# Bus_Definition_V1_2.net
KiCad netlist of a schematic drawn in EAGLE
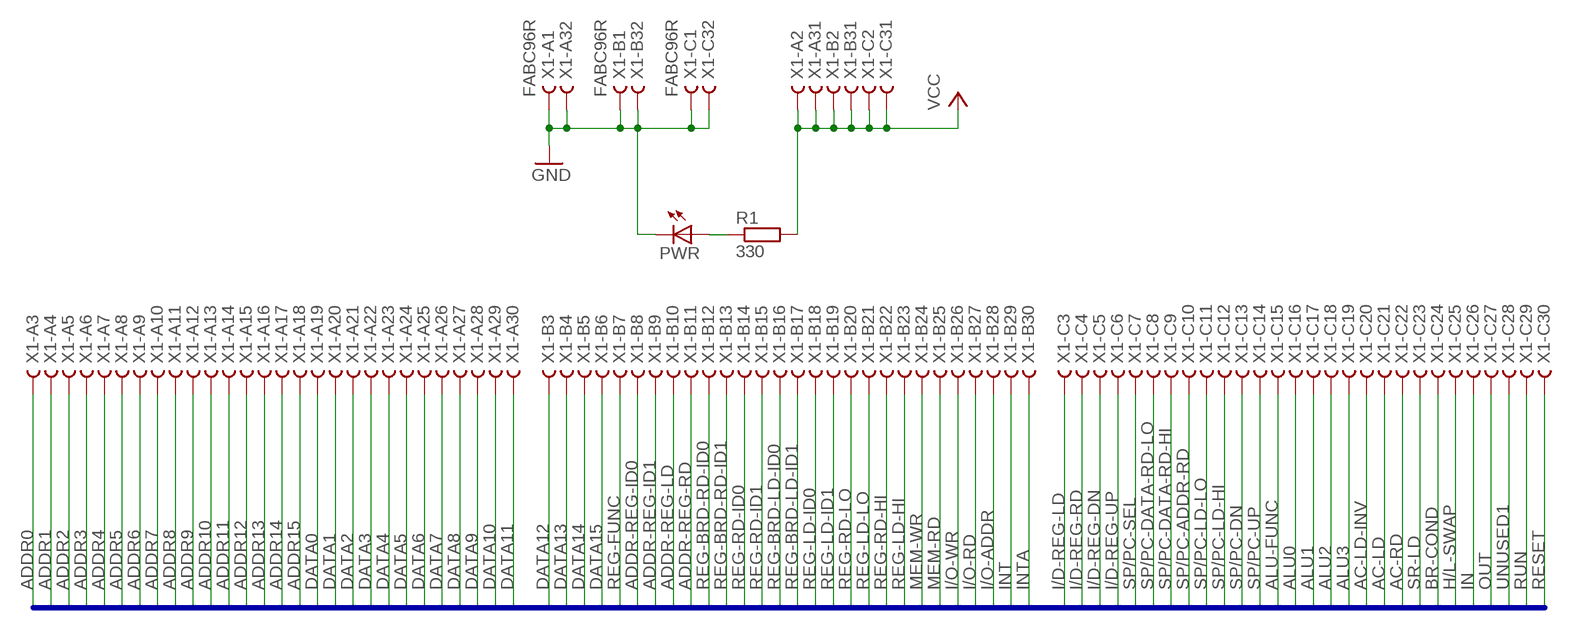
[diagram p0: schematic, sheet 1]

(export (version "E")
  (design (tool "Eeschema 10.0.6"))
  (components
    (comp (ref "PWR")
      (value "LED5MM")
      (footprint "eagle-import:LED5MM")
      (libsource (lib "eagle-import") (part "LED5MM"))
    )
    (comp (ref "R1")
      (value "330")
      (footprint "eagle-import:0207_10")
      (libsource (lib "eagle-import") (part "R0207/10"))
    )
    (comp (ref "X1")
      (value "FABC96R")
      (footprint "eagle-import:FABC96R")
      (libsource (lib "eagle-import") (part "FABC96R"))
    )
  )
  (nets
    (net (code "1") (name "/AC-LD") (class "Default")
      (node (ref "X1") (pin "C21") (pinfunction "B_C21") (pintype "passive"))
    )
    (net (code "2") (name "/AC-LD-INV") (class "Default")
      (node (ref "X1") (pin "C20") (pinfunction "B_C20") (pintype "passive"))
    )
    (net (code "3") (name "/AC-RD") (class "Default")
      (node (ref "X1") (pin "C22") (pinfunction "B_C22") (pintype "passive"))
    )
    (net (code "4") (name "/ADDR-REG-ID0") (class "Default")
      (node (ref "X1") (pin "B8") (pinfunction "B_B8") (pintype "passive"))
    )
    (net (code "5") (name "/ADDR-REG-ID1") (class "Default")
      (node (ref "X1") (pin "B9") (pinfunction "B_B9") (pintype "passive"))
    )
    (net (code "6") (name "/ADDR-REG-LD") (class "Default")
      (node (ref "X1") (pin "B10") (pinfunction "B_B10") (pintype "passive"))
    )
    (net (code "7") (name "/ADDR-REG-RD") (class "Default")
      (node (ref "X1") (pin "B11") (pinfunction "B_B11") (pintype "passive"))
    )
    (net (code "8") (name "/ADDR0") (class "Default")
      (node (ref "X1") (pin "A3") (pinfunction "B_A3") (pintype "passive"))
    )
    (net (code "9") (name "/ADDR1") (class "Default")
      (node (ref "X1") (pin "A4") (pinfunction "B_A4") (pintype "passive"))
    )
    (net (code "10") (name "/ADDR2") (class "Default")
      (node (ref "X1") (pin "A5") (pinfunction "B_A5") (pintype "passive"))
    )
    (net (code "11") (name "/ADDR3") (class "Default")
      (node (ref "X1") (pin "A6") (pinfunction "B_A6") (pintype "passive"))
    )
    (net (code "12") (name "/ADDR4") (class "Default")
      (node (ref "X1") (pin "A7") (pinfunction "B_A7") (pintype "passive"))
    )
    (net (code "13") (name "/ADDR5") (class "Default")
      (node (ref "X1") (pin "A8") (pinfunction "B_A8") (pintype "passive"))
    )
    (net (code "14") (name "/ADDR6") (class "Default")
      (node (ref "X1") (pin "A9") (pinfunction "B_A9") (pintype "passive"))
    )
    (net (code "15") (name "/ADDR7") (class "Default")
      (node (ref "X1") (pin "A10") (pinfunction "B_A10") (pintype "passive"))
    )
    (net (code "16") (name "/ADDR8") (class "Default")
      (node (ref "X1") (pin "A11") (pinfunction "B_A11") (pintype "passive"))
    )
    (net (code "17") (name "/ADDR9") (class "Default")
      (node (ref "X1") (pin "A12") (pinfunction "B_A12") (pintype "passive"))
    )
    (net (code "18") (name "/ADDR10") (class "Default")
      (node (ref "X1") (pin "A13") (pinfunction "B_A13") (pintype "passive"))
    )
    (net (code "19") (name "/ADDR11") (class "Default")
      (node (ref "X1") (pin "A14") (pinfunction "B_A14") (pintype "passive"))
    )
    (net (code "20") (name "/ADDR12") (class "Default")
      (node (ref "X1") (pin "A15") (pinfunction "B_A15") (pintype "passive"))
    )
    (net (code "21") (name "/ADDR13") (class "Default")
      (node (ref "X1") (pin "A16") (pinfunction "B_A16") (pintype "passive"))
    )
    (net (code "22") (name "/ADDR14") (class "Default")
      (node (ref "X1") (pin "A17") (pinfunction "B_A17") (pintype "passive"))
    )
    (net (code "23") (name "/ADDR15") (class "Default")
      (node (ref "X1") (pin "A18") (pinfunction "B_A18") (pintype "passive"))
    )
    (net (code "24") (name "/ALU-FUNC") (class "Default")
      (node (ref "X1") (pin "C15") (pinfunction "B_C15") (pintype "passive"))
    )
    (net (code "25") (name "/ALU0") (class "Default")
      (node (ref "X1") (pin "C16") (pinfunction "B_C16") (pintype "passive"))
    )
    (net (code "26") (name "/ALU1") (class "Default")
      (node (ref "X1") (pin "C17") (pinfunction "B_C17") (pintype "passive"))
    )
    (net (code "27") (name "/ALU2") (class "Default")
      (node (ref "X1") (pin "C18") (pinfunction "B_C18") (pintype "passive"))
    )
    (net (code "28") (name "/ALU3") (class "Default")
      (node (ref "X1") (pin "C19") (pinfunction "B_C19") (pintype "passive"))
    )
    (net (code "29") (name "/BR-COND") (class "Default")
      (node (ref "X1") (pin "C24") (pinfunction "B_C24") (pintype "passive"))
    )
    (net (code "30") (name "/DATA0") (class "Default")
      (node (ref "X1") (pin "A19") (pinfunction "B_A19") (pintype "passive"))
    )
    (net (code "31") (name "/DATA1") (class "Default")
      (node (ref "X1") (pin "A20") (pinfunction "B_A20") (pintype "passive"))
    )
    (net (code "32") (name "/DATA2") (class "Default")
      (node (ref "X1") (pin "A21") (pinfunction "B_A21") (pintype "passive"))
    )
    (net (code "33") (name "/DATA3") (class "Default")
      (node (ref "X1") (pin "A22") (pinfunction "B_A22") (pintype "passive"))
    )
    (net (code "34") (name "/DATA4") (class "Default")
      (node (ref "X1") (pin "A23") (pinfunction "B_A23") (pintype "passive"))
    )
    (net (code "35") (name "/DATA5") (class "Default")
      (node (ref "X1") (pin "A24") (pinfunction "B_A24") (pintype "passive"))
    )
    (net (code "36") (name "/DATA6") (class "Default")
      (node (ref "X1") (pin "A25") (pinfunction "B_A25") (pintype "passive"))
    )
    (net (code "37") (name "/DATA7") (class "Default")
      (node (ref "X1") (pin "A26") (pinfunction "B_A26") (pintype "passive"))
    )
    (net (code "38") (name "/DATA8") (class "Default")
      (node (ref "X1") (pin "A27") (pinfunction "B_A27") (pintype "passive"))
    )
    (net (code "39") (name "/DATA9") (class "Default")
      (node (ref "X1") (pin "A28") (pinfunction "B_A28") (pintype "passive"))
    )
    (net (code "40") (name "/DATA10") (class "Default")
      (node (ref "X1") (pin "A29") (pinfunction "B_A29") (pintype "passive"))
    )
    (net (code "41") (name "/DATA11") (class "Default")
      (node (ref "X1") (pin "A30") (pinfunction "B_A30") (pintype "passive"))
    )
    (net (code "42") (name "/DATA12") (class "Default")
      (node (ref "X1") (pin "B3") (pinfunction "B_B3") (pintype "passive"))
    )
    (net (code "43") (name "/DATA13") (class "Default")
      (node (ref "X1") (pin "B4") (pinfunction "B_B4") (pintype "passive"))
    )
    (net (code "44") (name "/DATA14") (class "Default")
      (node (ref "X1") (pin "B5") (pinfunction "B_B5") (pintype "passive"))
    )
    (net (code "45") (name "/DATA15") (class "Default")
      (node (ref "X1") (pin "B6") (pinfunction "B_B6") (pintype "passive"))
    )
    (net (code "46") (name "/H{slash}L-SWAP") (class "Default")
      (node (ref "X1") (pin "C25") (pinfunction "B_C25") (pintype "passive"))
    )
    (net (code "47") (name "/IN") (class "Default")
      (node (ref "X1") (pin "C26") (pinfunction "B_C26") (pintype "passive"))
    )
    (net (code "48") (name "/INT") (class "Default")
      (node (ref "X1") (pin "B29") (pinfunction "B_B29") (pintype "passive"))
    )
    (net (code "49") (name "/INTA") (class "Default")
      (node (ref "X1") (pin "B30") (pinfunction "B_B30") (pintype "passive"))
    )
    (net (code "50") (name "/I{slash}D-REG-DN") (class "Default")
      (node (ref "X1") (pin "C5") (pinfunction "B_C5") (pintype "passive"))
    )
    (net (code "51") (name "/I{slash}D-REG-LD") (class "Default")
      (node (ref "X1") (pin "C3") (pinfunction "B_C3") (pintype "passive"))
    )
    (net (code "52") (name "/I{slash}D-REG-RD") (class "Default")
      (node (ref "X1") (pin "C4") (pinfunction "B_C4") (pintype "passive"))
    )
    (net (code "53") (name "/I{slash}D-REG-UP") (class "Default")
      (node (ref "X1") (pin "C6") (pinfunction "B_C6") (pintype "passive"))
    )
    (net (code "54") (name "/I{slash}O-ADDR") (class "Default")
      (node (ref "X1") (pin "B28") (pinfunction "B_B28") (pintype "passive"))
    )
    (net (code "55") (name "/I{slash}O-RD") (class "Default")
      (node (ref "X1") (pin "B27") (pinfunction "B_B27") (pintype "passive"))
    )
    (net (code "56") (name "/I{slash}O-WR") (class "Default")
      (node (ref "X1") (pin "B26") (pinfunction "B_B26") (pintype "passive"))
    )
    (net (code "57") (name "/MEM-RD") (class "Default")
      (node (ref "X1") (pin "B25") (pinfunction "B_B25") (pintype "passive"))
    )
    (net (code "58") (name "/MEM-WR") (class "Default")
      (node (ref "X1") (pin "B24") (pinfunction "B_B24") (pintype "passive"))
    )
    (net (code "59") (name "/OUT") (class "Default")
      (node (ref "X1") (pin "C27") (pinfunction "B_C27") (pintype "passive"))
    )
    (net (code "60") (name "/REG-BRD-LD-ID0") (class "Default")
      (node (ref "X1") (pin "B16") (pinfunction "B_B16") (pintype "passive"))
    )
    (net (code "61") (name "/REG-BRD-LD-ID1") (class "Default")
      (node (ref "X1") (pin "B17") (pinfunction "B_B17") (pintype "passive"))
    )
    (net (code "62") (name "/REG-BRD-RD-ID0") (class "Default")
      (node (ref "X1") (pin "B12") (pinfunction "B_B12") (pintype "passive"))
    )
    (net (code "63") (name "/REG-BRD-RD-ID1") (class "Default")
      (node (ref "X1") (pin "B13") (pinfunction "B_B13") (pintype "passive"))
    )
    (net (code "64") (name "/REG-FUNC") (class "Default")
      (node (ref "X1") (pin "B7") (pinfunction "B_B7") (pintype "passive"))
    )
    (net (code "65") (name "/REG-LD-HI") (class "Default")
      (node (ref "X1") (pin "B23") (pinfunction "B_B23") (pintype "passive"))
    )
    (net (code "66") (name "/REG-LD-ID0") (class "Default")
      (node (ref "X1") (pin "B18") (pinfunction "B_B18") (pintype "passive"))
    )
    (net (code "67") (name "/REG-LD-ID1") (class "Default")
      (node (ref "X1") (pin "B19") (pinfunction "B_B19") (pintype "passive"))
    )
    (net (code "68") (name "/REG-LD-LO") (class "Default")
      (node (ref "X1") (pin "B21") (pinfunction "B_B21") (pintype "passive"))
    )
    (net (code "69") (name "/REG-RD-HI") (class "Default")
      (node (ref "X1") (pin "B22") (pinfunction "B_B22") (pintype "passive"))
    )
    (net (code "70") (name "/REG-RD-ID0") (class "Default")
      (node (ref "X1") (pin "B14") (pinfunction "B_B14") (pintype "passive"))
    )
    (net (code "71") (name "/REG-RD-ID1") (class "Default")
      (node (ref "X1") (pin "B15") (pinfunction "B_B15") (pintype "passive"))
    )
    (net (code "72") (name "/REG-RD-LO") (class "Default")
      (node (ref "X1") (pin "B20") (pinfunction "B_B20") (pintype "passive"))
    )
    (net (code "73") (name "/RESET") (class "Default")
      (node (ref "X1") (pin "C30") (pinfunction "B_C30") (pintype "passive"))
    )
    (net (code "74") (name "/RUN") (class "Default")
      (node (ref "X1") (pin "C29") (pinfunction "B_C29") (pintype "passive"))
    )
    (net (code "75") (name "/SP{slash}PC-ADDR-RD") (class "Default")
      (node (ref "X1") (pin "C10") (pinfunction "B_C10") (pintype "passive"))
    )
    (net (code "76") (name "/SP{slash}PC-DATA-RD-HI") (class "Default")
      (node (ref "X1") (pin "C9") (pinfunction "B_C9") (pintype "passive"))
    )
    (net (code "77") (name "/SP{slash}PC-DATA-RD-LO") (class "Default")
      (node (ref "X1") (pin "C8") (pinfunction "B_C8") (pintype "passive"))
    )
    (net (code "78") (name "/SP{slash}PC-DN") (class "Default")
      (node (ref "X1") (pin "C13") (pinfunction "B_C13") (pintype "passive"))
    )
    (net (code "79") (name "/SP{slash}PC-LD-HI") (class "Default")
      (node (ref "X1") (pin "C12") (pinfunction "B_C12") (pintype "passive"))
    )
    (net (code "80") (name "/SP{slash}PC-LD-LO") (class "Default")
      (node (ref "X1") (pin "C11") (pinfunction "B_C11") (pintype "passive"))
    )
    (net (code "81") (name "/SP{slash}PC-SEL") (class "Default")
      (node (ref "X1") (pin "C7") (pinfunction "B_C7") (pintype "passive"))
    )
    (net (code "82") (name "/SP{slash}PC-UP") (class "Default")
      (node (ref "X1") (pin "C14") (pinfunction "B_C14") (pintype "passive"))
    )
    (net (code "83") (name "/SR-LD") (class "Default")
      (node (ref "X1") (pin "C23") (pinfunction "B_C23") (pintype "passive"))
    )
    (net (code "84") (name "/UNUSED1") (class "Default")
      (node (ref "X1") (pin "C28") (pinfunction "B_C28") (pintype "passive"))
    )
    (net (code "85") (name "GND") (class "Default")
      (node (ref "PWR") (pin "K") (pinfunction "C_K") (pintype "passive"))
      (node (ref "X1") (pin "A1") (pinfunction "B_A1") (pintype "passive"))
      (node (ref "X1") (pin "A32") (pinfunction "B_A32") (pintype "passive"))
      (node (ref "X1") (pin "B1") (pinfunction "B_B1") (pintype "passive"))
      (node (ref "X1") (pin "B32") (pinfunction "B_B32") (pintype "passive"))
      (node (ref "X1") (pin "C1") (pinfunction "B_C1") (pintype "passive"))
      (node (ref "X1") (pin "C32") (pinfunction "B_C32") (pintype "passive"))
    )
    (net (code "86") (name "Net-(PWR-PadA)") (class "Default")
      (node (ref "PWR") (pin "A") (pinfunction "A_A") (pintype "passive"))
      (node (ref "R1") (pin "1") (pinfunction "1_1") (pintype "passive"))
    )
    (net (code "87") (name "VCC") (class "Default")
      (node (ref "R1") (pin "2") (pinfunction "2_2") (pintype "passive"))
      (node (ref "X1") (pin "A2") (pinfunction "B_A2") (pintype "passive"))
      (node (ref "X1") (pin "A31") (pinfunction "B_A31") (pintype "passive"))
      (node (ref "X1") (pin "B2") (pinfunction "B_B2") (pintype "passive"))
      (node (ref "X1") (pin "B31") (pinfunction "B_B31") (pintype "passive"))
      (node (ref "X1") (pin "C2") (pinfunction "B_C2") (pintype "passive"))
      (node (ref "X1") (pin "C31") (pinfunction "B_C31") (pintype "passive"))
    )
  )
)
